# motor_MCU.net
KiCad netlist of a schematic drawn in Altium Designer
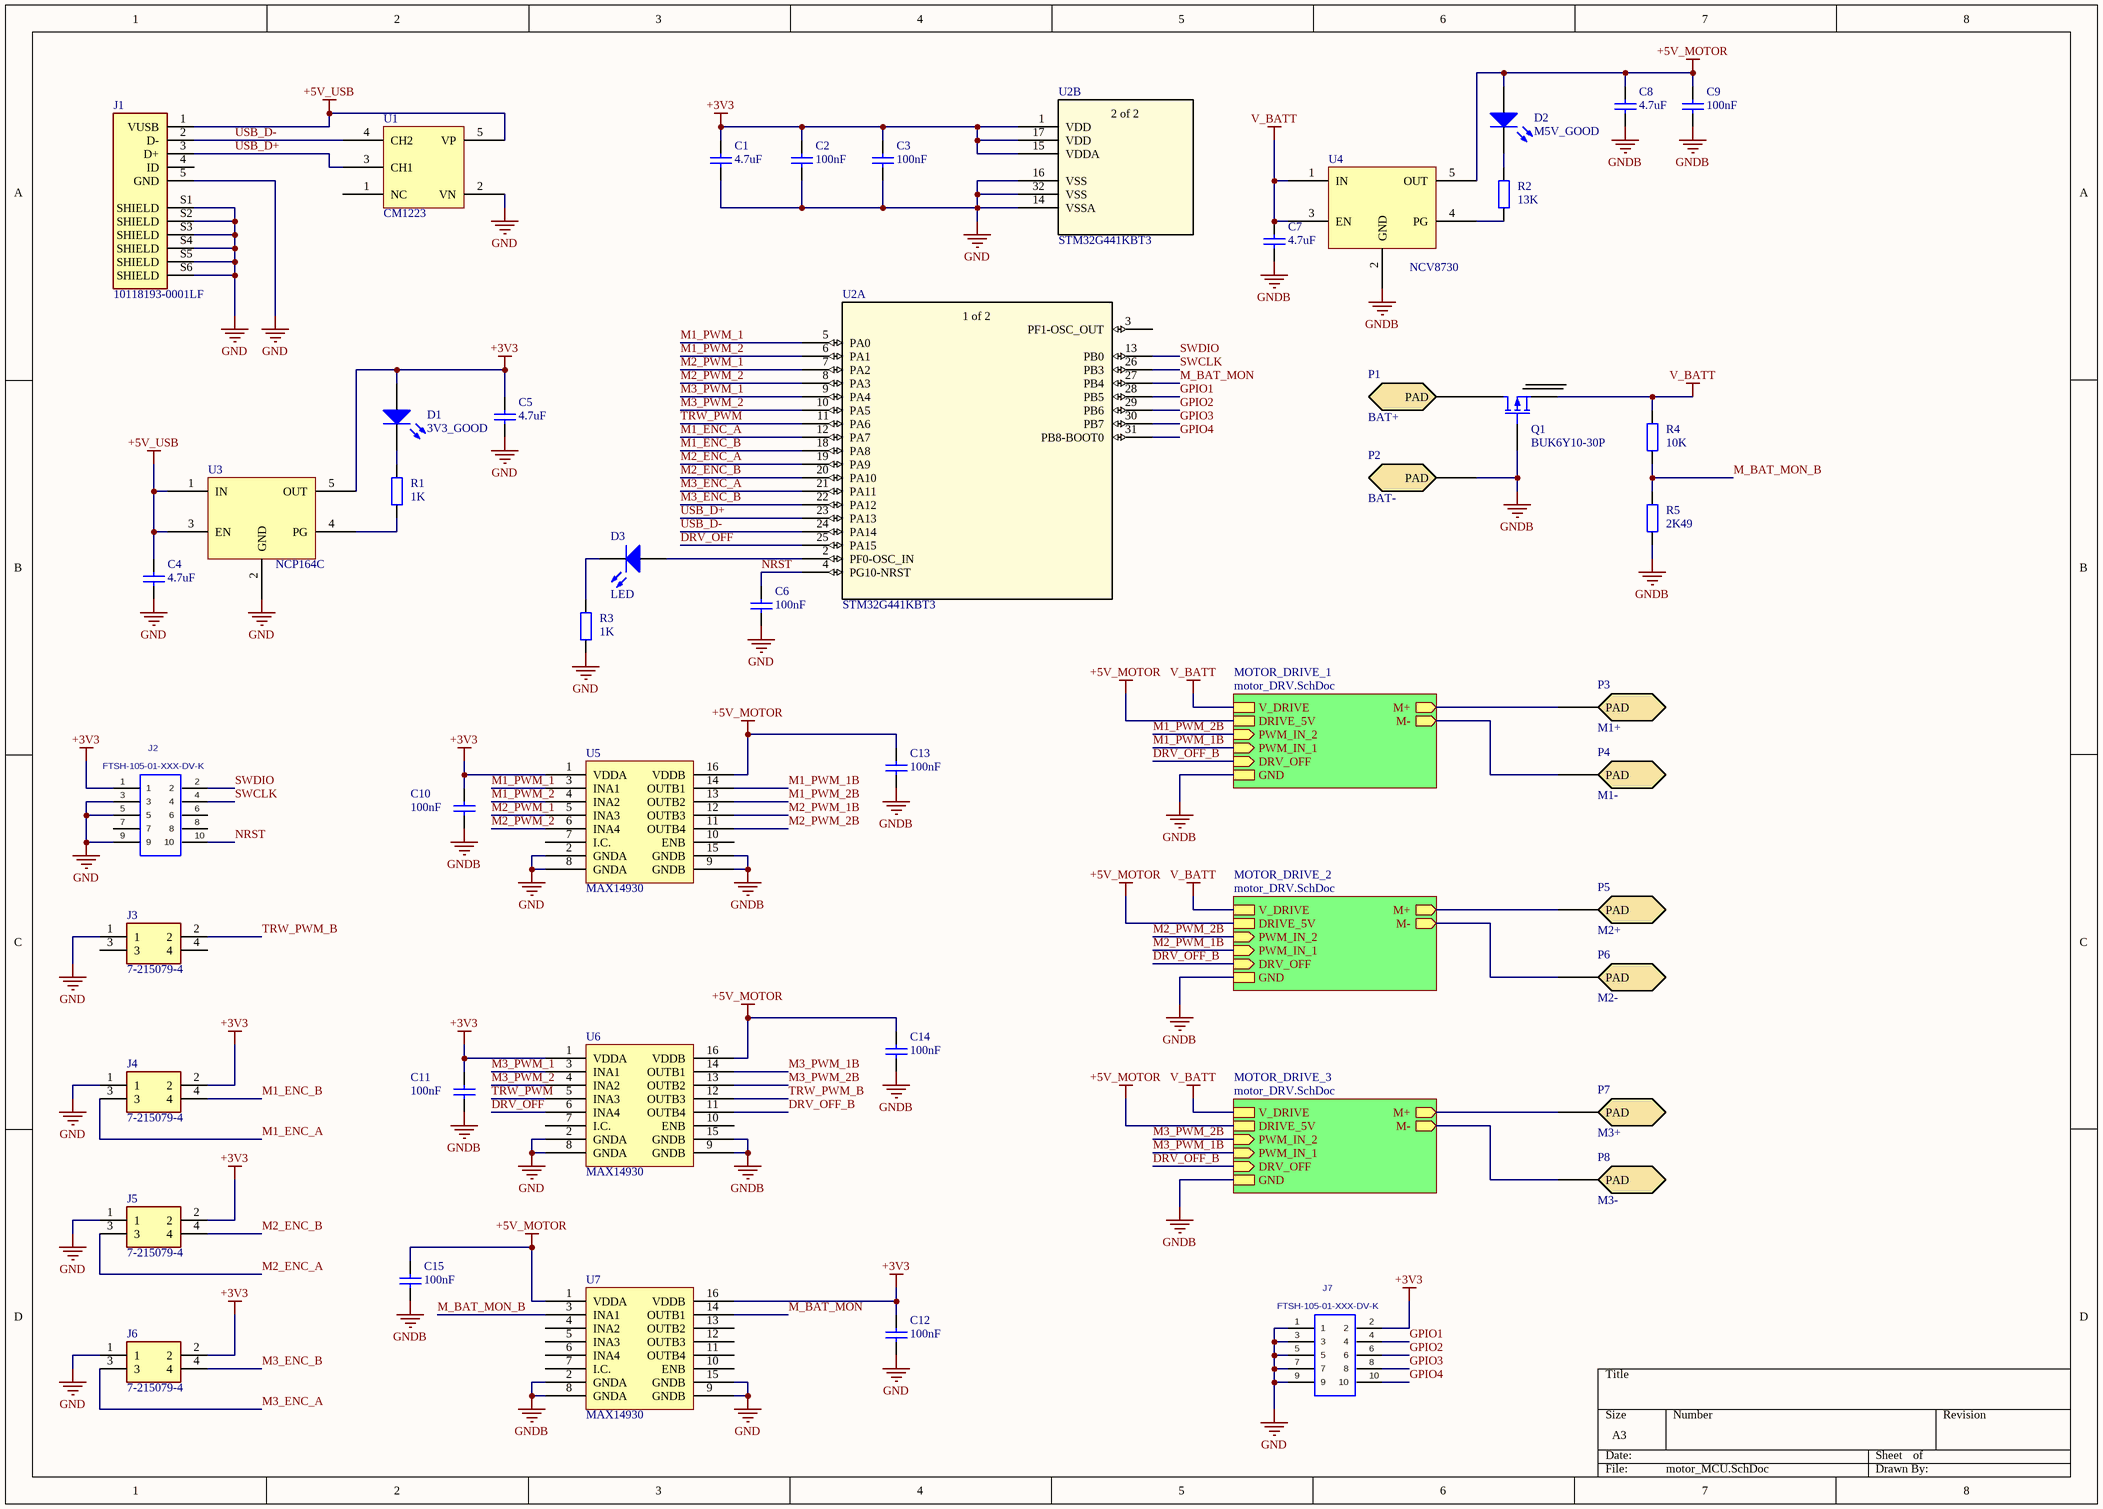
[diagram p0: motor_MCU.SchDoc]

(export (version "E")
  (design (tool "Eeschema 10.0.6"))
  (components
    (comp (ref "C1")
      (value "4.7uF")
      (footprint "C1206")
      (description "Capacitor (Semiconductor SIM Model)")
      (fields (field (name "Comment") "Cap Semi") (field (name "PUBLISHER") "Altium Limited"))
      (libsource (lib "Miscellaneous Devices") (part "Cap Semi"))
    )
    (comp (ref "C2")
      (value "100nF")
      (footprint "1608[0603]")
      (description "Capacitor (Semiconductor SIM Model)")
      (fields (field (name "Comment") "Cap Semi") (field (name "PUBLISHER") "Altium Limited"))
      (libsource (lib "Miscellaneous Devices") (part "Cap Semi"))
    )
    (comp (ref "C3")
      (value "100nF")
      (footprint "1608[0603]")
      (description "Capacitor (Semiconductor SIM Model)")
      (fields (field (name "Comment") "Cap Semi") (field (name "PUBLISHER") "Altium Limited"))
      (libsource (lib "Miscellaneous Devices") (part "Cap Semi"))
    )
    (comp (ref "C4")
      (value "4.7uF")
      (footprint "C1206")
      (description "Capacitor (Semiconductor SIM Model)")
      (fields (field (name "Comment") "Cap Semi") (field (name "PUBLISHER") "Altium Limited"))
      (libsource (lib "Miscellaneous Devices") (part "Cap Semi"))
    )
    (comp (ref "C5")
      (value "4.7uF")
      (footprint "C1206")
      (description "Capacitor (Semiconductor SIM Model)")
      (fields (field (name "Comment") "Cap Semi") (field (name "PUBLISHER") "Altium Limited"))
      (libsource (lib "Miscellaneous Devices") (part "Cap Semi"))
    )
    (comp (ref "C6")
      (value "100nF")
      (footprint "1608[0603]")
      (description "Capacitor (Semiconductor SIM Model)")
      (fields (field (name "Comment") "Cap Semi") (field (name "PUBLISHER") "Altium Limited"))
      (libsource (lib "Miscellaneous Devices") (part "Cap Semi"))
    )
    (comp (ref "C7")
      (value "4.7uF")
      (footprint "C1206")
      (description "Capacitor (Semiconductor SIM Model)")
      (fields (field (name "Comment") "Cap Semi") (field (name "PUBLISHER") "Altium Limited"))
      (libsource (lib "Miscellaneous Devices") (part "Cap Semi"))
    )
    (comp (ref "C8")
      (value "4.7uF")
      (footprint "C1206")
      (description "Capacitor (Semiconductor SIM Model)")
      (fields (field (name "Comment") "Cap Semi") (field (name "PUBLISHER") "Altium Limited"))
      (libsource (lib "Miscellaneous Devices") (part "Cap Semi"))
    )
    (comp (ref "C9")
      (value "100nF")
      (footprint "1608[0603]")
      (description "Capacitor (Semiconductor SIM Model)")
      (fields (field (name "Comment") "Cap Semi") (field (name "PUBLISHER") "Altium Limited"))
      (libsource (lib "Miscellaneous Devices") (part "Cap Semi"))
    )
    (comp (ref "C10")
      (value "100nF")
      (footprint "1608[0603]")
      (description "Capacitor (Semiconductor SIM Model)")
      (fields (field (name "Comment") "Cap Semi") (field (name "PUBLISHER") "Altium Limited"))
      (libsource (lib "Miscellaneous Devices") (part "Cap Semi"))
    )
    (comp (ref "C11")
      (value "100nF")
      (footprint "1608[0603]")
      (description "Capacitor (Semiconductor SIM Model)")
      (fields (field (name "Comment") "Cap Semi") (field (name "PUBLISHER") "Altium Limited"))
      (libsource (lib "Miscellaneous Devices") (part "Cap Semi"))
    )
    (comp (ref "C12")
      (value "100nF")
      (footprint "1608[0603]")
      (description "Capacitor (Semiconductor SIM Model)")
      (fields (field (name "Comment") "Cap Semi") (field (name "PUBLISHER") "Altium Limited"))
      (libsource (lib "Miscellaneous Devices") (part "Cap Semi"))
    )
    (comp (ref "C13")
      (value "100nF")
      (footprint "1608[0603]")
      (description "Capacitor (Semiconductor SIM Model)")
      (fields (field (name "Comment") "Cap Semi") (field (name "PUBLISHER") "Altium Limited"))
      (libsource (lib "Miscellaneous Devices") (part "Cap Semi"))
    )
    (comp (ref "C14")
      (value "100nF")
      (footprint "1608[0603]")
      (description "Capacitor (Semiconductor SIM Model)")
      (fields (field (name "Comment") "Cap Semi") (field (name "PUBLISHER") "Altium Limited"))
      (libsource (lib "Miscellaneous Devices") (part "Cap Semi"))
    )
    (comp (ref "C15")
      (value "100nF")
      (footprint "1608[0603]")
      (description "Capacitor (Semiconductor SIM Model)")
      (fields (field (name "Comment") "Cap Semi") (field (name "PUBLISHER") "Altium Limited"))
      (libsource (lib "Miscellaneous Devices") (part "Cap Semi"))
    )
    (comp (ref "D1")
      (value "3V3_GOOD")
      (footprint "3.2X1.6X1.1")
      (description "Typical RED, GREEN, YELLOW, AMBER GaAs LED")
      (fields (field (name "PUBLISHER") "Altium Limited"))
      (libsource (lib "Miscellaneous Devices") (part "LED2"))
    )
    (comp (ref "D2")
      (value "M5V_GOOD")
      (footprint "3.2X1.6X1.1")
      (description "Typical RED, GREEN, YELLOW, AMBER GaAs LED")
      (fields (field (name "PUBLISHER") "Altium Limited"))
      (libsource (lib "Miscellaneous Devices") (part "LED2"))
    )
    (comp (ref "D3")
      (value "LED")
      (footprint "3.2X1.6X1.1")
      (description "Typical RED, GREEN, YELLOW, AMBER GaAs LED")
      (fields (field (name "PUBLISHER") "Altium Limited"))
      (libsource (lib "Miscellaneous Devices") (part "LED2"))
    )
    (comp (ref "J1")
      (value "10118193-0001LF")
      (footprint "FCI_10118193-0001LF")
      (description "USB - micro B USB 2.0 Receptacle Connector 5 Position Surface Mount, Right Angle; Through Hole")
      (fields (field (name "MF") "Amphenol ICC"))
      (libsource (lib "10118193-0001LF") (part "10118193-0001LF"))
    )
    (comp (ref "J2")
      (value "FTSH-105-01-XXX-DV-K")
      (footprint "FTSH-105-01-XXX-DV-K")
      (description "TERMINAL STRIP, .050\"(1.27mm) PITCH, 10 PINS, KEYED")
      (fields (field (name "MANUFACTURER") "SAMTEC") (field (name "CREATED") "November 30, 2016 - Wendy Xin"))
      (libsource (lib "FTSH-105-01-XXX-DV-K--Symbol-Altium-44987") (part "FTSH-105-01-XXX-DV-K"))
    )
    (comp (ref "J3")
      (value "7-215079-4")
      (footprint "TE_7-215079-4")
      (description "Micro-MaTch 4 Position 1.27 mm Pitch Vertical Female-on-Board Connector")
      (fields (field (name "MF") "TE Connectivity"))
      (libsource (lib "7-215079-4") (part "7-215079-4"))
    )
    (comp (ref "J4")
      (value "7-215079-4")
      (footprint "TE_7-215079-4")
      (description "Micro-MaTch 4 Position 1.27 mm Pitch Vertical Female-on-Board Connector")
      (fields (field (name "MF") "TE Connectivity"))
      (libsource (lib "7-215079-4") (part "7-215079-4"))
    )
    (comp (ref "J5")
      (value "7-215079-4")
      (footprint "TE_7-215079-4")
      (description "Micro-MaTch 4 Position 1.27 mm Pitch Vertical Female-on-Board Connector")
      (fields (field (name "MF") "TE Connectivity"))
      (libsource (lib "7-215079-4") (part "7-215079-4"))
    )
    (comp (ref "J6")
      (value "7-215079-4")
      (footprint "TE_7-215079-4")
      (description "Micro-MaTch 4 Position 1.27 mm Pitch Vertical Female-on-Board Connector")
      (fields (field (name "MF") "TE Connectivity"))
      (libsource (lib "7-215079-4") (part "7-215079-4"))
    )
    (comp (ref "J7")
      (value "FTSH-105-01-XXX-DV-K")
      (footprint "FTSH-105-01-XXX-DV-K")
      (description "TERMINAL STRIP, .050\"(1.27mm) PITCH, 10 PINS, KEYED")
      (fields (field (name "MANUFACTURER") "SAMTEC") (field (name "CREATED") "November 30, 2016 - Wendy Xin"))
      (libsource (lib "FTSH-105-01-XXX-DV-K--Symbol-Altium-44987") (part "FTSH-105-01-XXX-DV-K"))
    )
    (comp (ref "P1")
      (value "BAT+")
      (footprint "PCBComponent_1")
      (libsource (lib "powerpad140x175") (part "Component_1"))
    )
    (comp (ref "P2")
      (value "BAT-")
      (footprint "PCBComponent_1")
      (libsource (lib "powerpad140x175") (part "Component_1"))
    )
    (comp (ref "P3")
      (value "M1+")
      (footprint "PCBComponent_1")
      (libsource (lib "powerpad140x175") (part "Component_1"))
    )
    (comp (ref "P4")
      (value "M1-")
      (footprint "PCBComponent_1")
      (libsource (lib "powerpad140x175") (part "Component_1"))
    )
    (comp (ref "P5")
      (value "M2+")
      (footprint "PCBComponent_1")
      (libsource (lib "powerpad140x175") (part "Component_1"))
    )
    (comp (ref "P6")
      (value "M2-")
      (footprint "PCBComponent_1")
      (libsource (lib "powerpad140x175") (part "Component_1"))
    )
    (comp (ref "P7")
      (value "M3+")
      (footprint "PCBComponent_1")
      (libsource (lib "powerpad140x175") (part "Component_1"))
    )
    (comp (ref "P8")
      (value "M3-")
      (footprint "PCBComponent_1")
      (libsource (lib "powerpad140x175") (part "Component_1"))
    )
    (comp (ref "Q1")
      (value "BUK6Y10-30P")
      (footprint "TO127P600X120-5N")
      (description "P-Channel MOSFET")
      (fields (field (name "PUBLISHER") "Altium Limited"))
      (libsource (lib "Miscellaneous Devices") (part "MOSFET-P"))
    )
    (comp (ref "R1")
      (value "1K")
      (footprint "CAPC2012X135N")
      (description "Resistor")
      (fields (field (name "Comment") "Res2") (field (name "PUBLISHER") "Altium Limited"))
      (libsource (lib "Miscellaneous Devices") (part "Res2"))
    )
    (comp (ref "R2")
      (value "13K")
      (footprint "CAPC2012X135N")
      (description "Resistor")
      (fields (field (name "Comment") "Res2") (field (name "PUBLISHER") "Altium Limited"))
      (libsource (lib "Miscellaneous Devices") (part "Res2"))
    )
    (comp (ref "R3")
      (value "1K")
      (footprint "CAPC2012X135N")
      (description "Resistor")
      (fields (field (name "Comment") "Res2") (field (name "PUBLISHER") "Altium Limited"))
      (libsource (lib "Miscellaneous Devices") (part "Res2"))
    )
    (comp (ref "R4")
      (value "10K")
      (footprint "CAPC2012X135N")
      (description "Resistor")
      (fields (field (name "Comment") "Res2") (field (name "PUBLISHER") "Altium Limited"))
      (libsource (lib "Miscellaneous Devices") (part "Res2"))
    )
    (comp (ref "R5")
      (value "2K49")
      (footprint "CAPC2012X135N")
      (description "Resistor")
      (fields (field (name "Comment") "Res2") (field (name "PUBLISHER") "Altium Limited"))
      (libsource (lib "Miscellaneous Devices") (part "Res2"))
    )
    (comp (ref "U1") (value "CM1223") (footprint "SOT23-5") (libsource (lib "CM1223-02SO") (part "CM1223")))
    (comp (ref "U2")
      (value "STM32G441KBT3")
      (footprint "LQFP32_7X7_STM")
      (description "No Description Available")
      (fields (field (name "COPYRIGHT") "Copyright (C) 2018 Accelerated Designs. All rights reserved"))
      (libsource (lib "STM32G441KBT3") (part "STM32G441KBT3"))
    )
    (comp (ref "U3") (value "NCP164C") (footprint "SOT23-5") (libsource (lib "NCP164C") (part "NCP164C")))
    (comp (ref "U4")
      (value "NCV8730")
      (footprint "TSSOP5")
      (description "5V LDO")
      (libsource (lib "NCV8730") (part "NCV8730"))
    )
    (comp (ref "U5")
      (value "MAX14930")
      (footprint "SOIC127P1030X265-16N")
      (libsource (lib "MAX14930") (part "MAX14930"))
    )
    (comp (ref "U6")
      (value "MAX14930")
      (footprint "SOIC127P1030X265-16N")
      (libsource (lib "MAX14930") (part "MAX14930"))
    )
    (comp (ref "U7")
      (value "MAX14930")
      (footprint "SOIC127P1030X265-16N")
      (libsource (lib "MAX14930") (part "MAX14930"))
    )
  )
  (nets
    (net (code "1") (name "+3V3") (class "Default")
      (node (ref "C1") (pin "2") (pinfunction "2_2") (pintype "passive"))
      (node (ref "C10") (pin "2") (pinfunction "2_2") (pintype "passive"))
      (node (ref "C11") (pin "2") (pinfunction "2_2") (pintype "passive"))
      (node (ref "C12") (pin "2") (pinfunction "2_2") (pintype "passive"))
      (node (ref "C2") (pin "2") (pinfunction "2_2") (pintype "passive"))
      (node (ref "C3") (pin "2") (pinfunction "2_2") (pintype "passive"))
      (node (ref "C5") (pin "2") (pinfunction "2_2") (pintype "passive"))
      (node (ref "D1") (pin "1") (pinfunction "A_1") (pintype "passive"))
      (node (ref "J2") (pin "1") (pinfunction "1_1") (pintype "passive"))
      (node (ref "J4") (pin "2") (pinfunction "2_2") (pintype "passive"))
      (node (ref "J5") (pin "2") (pinfunction "2_2") (pintype "passive"))
      (node (ref "J6") (pin "2") (pinfunction "2_2") (pintype "passive"))
      (node (ref "J7") (pin "2") (pinfunction "2_2") (pintype "passive"))
      (node (ref "U2") (pin "1") (pinfunction "VDD_1") (pintype "power_in"))
      (node (ref "U2") (pin "15") (pinfunction "VDDA_15") (pintype "power_in"))
      (node (ref "U2") (pin "17") (pinfunction "VDD_17") (pintype "power_in"))
      (node (ref "U3") (pin "5") (pinfunction "OUT_5") (pintype "passive"))
      (node (ref "U5") (pin "1") (pinfunction "VDDA_1") (pintype "passive"))
      (node (ref "U6") (pin "1") (pinfunction "VDDA_1") (pintype "passive"))
      (node (ref "U7") (pin "16") (pinfunction "VDDB_16") (pintype "passive"))
    )
    (net (code "2") (name "+5V_MOTOR") (class "Default")
      (node (ref "C13") (pin "2") (pinfunction "2_2") (pintype "passive"))
      (node (ref "C14") (pin "2") (pinfunction "2_2") (pintype "passive"))
      (node (ref "C15") (pin "2") (pinfunction "2_2") (pintype "passive"))
      (node (ref "C8") (pin "2") (pinfunction "2_2") (pintype "passive"))
      (node (ref "C9") (pin "2") (pinfunction "2_2") (pintype "passive"))
      (node (ref "D2") (pin "1") (pinfunction "A_1") (pintype "passive"))
      (node (ref "U4") (pin "5") (pinfunction "OUT_5") (pintype "passive"))
      (node (ref "U5") (pin "16") (pinfunction "VDDB_16") (pintype "passive"))
      (node (ref "U6") (pin "16") (pinfunction "VDDB_16") (pintype "passive"))
      (node (ref "U7") (pin "1") (pinfunction "VDDA_1") (pintype "passive"))
    )
    (net (code "3") (name "+5V_USB") (class "Default")
      (node (ref "C4") (pin "2") (pinfunction "2_2") (pintype "passive"))
      (node (ref "J1") (pin "1") (pinfunction "VUSB_1") (pintype "passive"))
      (node (ref "U1") (pin "5") (pinfunction "VP_5") (pintype "passive"))
      (node (ref "U3") (pin "1") (pinfunction "IN_1") (pintype "passive"))
      (node (ref "U3") (pin "3") (pinfunction "EN_3") (pintype "passive"))
    )
    (net (code "4") (name "/DRV_OFF") (class "Default")
      (node (ref "U2") (pin "25") (pinfunction "PA15_25") (pintype "bidirectional"))
      (node (ref "U6") (pin "6") (pinfunction "INA4_6") (pintype "passive"))
    )
    (net (code "5") (name "/DRV_OFF_B") (class "Default")
      (node (ref "U6") (pin "11") (pinfunction "OUTB4_11") (pintype "passive"))
    )
    (net (code "6") (name "/GPIO1") (class "Default")
      (node (ref "J7") (pin "4") (pinfunction "4_4") (pintype "passive"))
      (node (ref "U2") (pin "28") (pinfunction "PB5_28") (pintype "bidirectional"))
    )
    (net (code "7") (name "/GPIO2") (class "Default")
      (node (ref "J7") (pin "6") (pinfunction "6_6") (pintype "passive"))
      (node (ref "U2") (pin "29") (pinfunction "PB6_29") (pintype "bidirectional"))
    )
    (net (code "8") (name "/GPIO3") (class "Default")
      (node (ref "J7") (pin "8") (pinfunction "8_8") (pintype "passive"))
      (node (ref "U2") (pin "30") (pinfunction "PB7_30") (pintype "bidirectional"))
    )
    (net (code "9") (name "/GPIO4") (class "Default")
      (node (ref "J7") (pin "10") (pinfunction "10_10") (pintype "passive"))
      (node (ref "U2") (pin "31") (pinfunction "PB8-BOOT0_31") (pintype "bidirectional"))
    )
    (net (code "10") (name "/M+") (class "Default")
      (node (ref "P7") (pin "1") (pinfunction "PAD_1") (pintype "passive"))
    )
    (net (code "11") (name "/M+_1") (class "Default")
      (node (ref "P3") (pin "1") (pinfunction "PAD_1") (pintype "passive"))
    )
    (net (code "12") (name "/M+_2") (class "Default")
      (node (ref "P5") (pin "1") (pinfunction "PAD_1") (pintype "passive"))
    )
    (net (code "13") (name "/M-") (class "Default")
      (node (ref "P8") (pin "1") (pinfunction "PAD_1") (pintype "passive"))
    )
    (net (code "14") (name "/M-_1") (class "Default")
      (node (ref "P4") (pin "1") (pinfunction "PAD_1") (pintype "passive"))
    )
    (net (code "15") (name "/M-_2") (class "Default")
      (node (ref "P6") (pin "1") (pinfunction "PAD_1") (pintype "passive"))
    )
    (net (code "16") (name "/M1_ENC_A") (class "Default")
      (node (ref "J4") (pin "3") (pinfunction "3_3") (pintype "passive"))
      (node (ref "U2") (pin "12") (pinfunction "PA7_12") (pintype "bidirectional"))
    )
    (net (code "17") (name "/M1_ENC_B") (class "Default")
      (node (ref "J4") (pin "4") (pinfunction "4_4") (pintype "passive"))
      (node (ref "U2") (pin "18") (pinfunction "PA8_18") (pintype "bidirectional"))
    )
    (net (code "18") (name "/M1_PWM_1") (class "Default")
      (node (ref "U2") (pin "5") (pinfunction "PA0_5") (pintype "bidirectional"))
      (node (ref "U5") (pin "3") (pinfunction "INA1_3") (pintype "passive"))
    )
    (net (code "19") (name "/M1_PWM_1B") (class "Default")
      (node (ref "U5") (pin "14") (pinfunction "OUTB1_14") (pintype "passive"))
    )
    (net (code "20") (name "/M1_PWM_2") (class "Default")
      (node (ref "U2") (pin "6") (pinfunction "PA1_6") (pintype "bidirectional"))
      (node (ref "U5") (pin "4") (pinfunction "INA2_4") (pintype "passive"))
    )
    (net (code "21") (name "/M1_PWM_2B") (class "Default")
      (node (ref "U5") (pin "13") (pinfunction "OUTB2_13") (pintype "passive"))
    )
    (net (code "22") (name "/M2_ENC_A") (class "Default")
      (node (ref "J5") (pin "3") (pinfunction "3_3") (pintype "passive"))
      (node (ref "U2") (pin "19") (pinfunction "PA9_19") (pintype "bidirectional"))
    )
    (net (code "23") (name "/M2_ENC_B") (class "Default")
      (node (ref "J5") (pin "4") (pinfunction "4_4") (pintype "passive"))
      (node (ref "U2") (pin "20") (pinfunction "PA10_20") (pintype "bidirectional"))
    )
    (net (code "24") (name "/M2_PWM_1") (class "Default")
      (node (ref "U2") (pin "7") (pinfunction "PA2_7") (pintype "bidirectional"))
      (node (ref "U5") (pin "5") (pinfunction "INA3_5") (pintype "passive"))
    )
    (net (code "25") (name "/M2_PWM_1B") (class "Default")
      (node (ref "U5") (pin "12") (pinfunction "OUTB3_12") (pintype "passive"))
    )
    (net (code "26") (name "/M2_PWM_2") (class "Default")
      (node (ref "U2") (pin "8") (pinfunction "PA3_8") (pintype "bidirectional"))
      (node (ref "U5") (pin "6") (pinfunction "INA4_6") (pintype "passive"))
    )
    (net (code "27") (name "/M2_PWM_2B") (class "Default")
      (node (ref "U5") (pin "11") (pinfunction "OUTB4_11") (pintype "passive"))
    )
    (net (code "28") (name "/M3_ENC_A") (class "Default")
      (node (ref "J6") (pin "3") (pinfunction "3_3") (pintype "passive"))
      (node (ref "U2") (pin "21") (pinfunction "PA11_21") (pintype "bidirectional"))
    )
    (net (code "29") (name "/M3_ENC_B") (class "Default")
      (node (ref "J6") (pin "4") (pinfunction "4_4") (pintype "passive"))
      (node (ref "U2") (pin "22") (pinfunction "PA12_22") (pintype "bidirectional"))
    )
    (net (code "30") (name "/M3_PWM_1") (class "Default")
      (node (ref "U2") (pin "9") (pinfunction "PA4_9") (pintype "bidirectional"))
      (node (ref "U6") (pin "3") (pinfunction "INA1_3") (pintype "passive"))
    )
    (net (code "31") (name "/M3_PWM_1B") (class "Default")
      (node (ref "U6") (pin "14") (pinfunction "OUTB1_14") (pintype "passive"))
    )
    (net (code "32") (name "/M3_PWM_2") (class "Default")
      (node (ref "U2") (pin "10") (pinfunction "PA5_10") (pintype "bidirectional"))
      (node (ref "U6") (pin "4") (pinfunction "INA2_4") (pintype "passive"))
    )
    (net (code "33") (name "/M3_PWM_2B") (class "Default")
      (node (ref "U6") (pin "13") (pinfunction "OUTB2_13") (pintype "passive"))
    )
    (net (code "34") (name "/M_BAT_MON") (class "Default")
      (node (ref "U2") (pin "27") (pinfunction "PB4_27") (pintype "bidirectional"))
      (node (ref "U7") (pin "14") (pinfunction "OUTB1_14") (pintype "passive"))
    )
    (net (code "35") (name "/M_BAT_MON_B") (class "Default")
      (node (ref "R4") (pin "1") (pinfunction "1_1") (pintype "passive"))
      (node (ref "R5") (pin "2") (pinfunction "2_2") (pintype "passive"))
      (node (ref "U7") (pin "3") (pinfunction "INA1_3") (pintype "passive"))
    )
    (net (code "36") (name "/NRST") (class "Default")
      (node (ref "C6") (pin "2") (pinfunction "2_2") (pintype "passive"))
      (node (ref "J2") (pin "10") (pinfunction "10_10") (pintype "passive"))
      (node (ref "U2") (pin "4") (pinfunction "PG10-NRST_4") (pintype "bidirectional"))
    )
    (net (code "37") (name "/SWCLK") (class "Default")
      (node (ref "J2") (pin "4") (pinfunction "4_4") (pintype "passive"))
      (node (ref "U2") (pin "26") (pinfunction "PB3_26") (pintype "bidirectional"))
    )
    (net (code "38") (name "/SWDIO") (class "Default")
      (node (ref "J2") (pin "2") (pinfunction "2_2") (pintype "passive"))
      (node (ref "U2") (pin "13") (pinfunction "PB0_13") (pintype "bidirectional"))
    )
    (net (code "39") (name "/TRW_PWM") (class "Default")
      (node (ref "U2") (pin "11") (pinfunction "PA6_11") (pintype "bidirectional"))
      (node (ref "U6") (pin "5") (pinfunction "INA3_5") (pintype "passive"))
    )
    (net (code "40") (name "/TRW_PWM_B") (class "Default")
      (node (ref "J3") (pin "2") (pinfunction "2_2") (pintype "passive"))
      (node (ref "U6") (pin "12") (pinfunction "OUTB3_12") (pintype "passive"))
    )
    (net (code "41") (name "/USB_D+") (class "Default")
      (node (ref "J1") (pin "3") (pinfunction "D+_3") (pintype "passive"))
      (node (ref "U1") (pin "3") (pinfunction "CH1_3") (pintype "passive"))
      (node (ref "U2") (pin "23") (pinfunction "PA13_23") (pintype "bidirectional"))
    )
    (net (code "42") (name "/USB_D-") (class "Default")
      (node (ref "J1") (pin "2") (pinfunction "D-_2") (pintype "passive"))
      (node (ref "U1") (pin "4") (pinfunction "CH2_4") (pintype "passive"))
      (node (ref "U2") (pin "24") (pinfunction "PA14_24") (pintype "bidirectional"))
    )
    (net (code "43") (name "GND") (class "Default")
      (node (ref "C1") (pin "1") (pinfunction "1_1") (pintype "passive"))
      (node (ref "C12") (pin "1") (pinfunction "1_1") (pintype "passive"))
      (node (ref "C2") (pin "1") (pinfunction "1_1") (pintype "passive"))
      (node (ref "C3") (pin "1") (pinfunction "1_1") (pintype "passive"))
      (node (ref "C4") (pin "1") (pinfunction "1_1") (pintype "passive"))
      (node (ref "C5") (pin "1") (pinfunction "1_1") (pintype "passive"))
      (node (ref "C6") (pin "1") (pinfunction "1_1") (pintype "passive"))
      (node (ref "J1") (pin "5") (pinfunction "GND_5") (pintype "passive"))
      (node (ref "J1") (pin "S1") (pinfunction "SHIELD_S1") (pintype "passive"))
      (node (ref "J1") (pin "S2") (pinfunction "SHIELD_S2") (pintype "passive"))
      (node (ref "J1") (pin "S3") (pinfunction "SHIELD_S3") (pintype "passive"))
      (node (ref "J1") (pin "S4") (pinfunction "SHIELD_S4") (pintype "passive"))
      (node (ref "J1") (pin "S5") (pinfunction "SHIELD_S5") (pintype "passive"))
      (node (ref "J1") (pin "S6") (pinfunction "SHIELD_S6") (pintype "passive"))
      (node (ref "J2") (pin "3") (pinfunction "3_3") (pintype "passive"))
      (node (ref "J2") (pin "5") (pinfunction "5_5") (pintype "passive"))
      (node (ref "J2") (pin "9") (pinfunction "9_9") (pintype "passive"))
      (node (ref "J3") (pin "1") (pinfunction "1_1") (pintype "passive"))
      (node (ref "J4") (pin "1") (pinfunction "1_1") (pintype "passive"))
      (node (ref "J5") (pin "1") (pinfunction "1_1") (pintype "passive"))
      (node (ref "J6") (pin "1") (pinfunction "1_1") (pintype "passive"))
      (node (ref "J7") (pin "1") (pinfunction "1_1") (pintype "passive"))
      (node (ref "J7") (pin "3") (pinfunction "3_3") (pintype "passive"))
      (node (ref "J7") (pin "5") (pinfunction "5_5") (pintype "passive"))
      (node (ref "J7") (pin "7") (pinfunction "7_7") (pintype "passive"))
      (node (ref "J7") (pin "9") (pinfunction "9_9") (pintype "passive"))
      (node (ref "R3") (pin "1") (pinfunction "1_1") (pintype "passive"))
      (node (ref "U1") (pin "2") (pinfunction "VN_2") (pintype "passive"))
      (node (ref "U2") (pin "14") (pinfunction "VSSA_14") (pintype "passive"))
      (node (ref "U2") (pin "16") (pinfunction "VSS_16") (pintype "passive"))
      (node (ref "U2") (pin "32") (pinfunction "VSS_32") (pintype "passive"))
      (node (ref "U3") (pin "2") (pinfunction "GND_2") (pintype "passive"))
      (node (ref "U5") (pin "2") (pinfunction "GNDA_2") (pintype "passive"))
      (node (ref "U5") (pin "8") (pinfunction "GNDA_8") (pintype "passive"))
      (node (ref "U6") (pin "2") (pinfunction "GNDA_2") (pintype "passive"))
      (node (ref "U6") (pin "8") (pinfunction "GNDA_8") (pintype "passive"))
      (node (ref "U7") (pin "15") (pinfunction "GNDB_15") (pintype "passive"))
      (node (ref "U7") (pin "9") (pinfunction "GNDB_9") (pintype "passive"))
    )
    (net (code "44") (name "GNDB") (class "Default")
      (node (ref "C10") (pin "1") (pinfunction "1_1") (pintype "passive"))
      (node (ref "C11") (pin "1") (pinfunction "1_1") (pintype "passive"))
      (node (ref "C13") (pin "1") (pinfunction "1_1") (pintype "passive"))
      (node (ref "C14") (pin "1") (pinfunction "1_1") (pintype "passive"))
      (node (ref "C15") (pin "1") (pinfunction "1_1") (pintype "passive"))
      (node (ref "C7") (pin "1") (pinfunction "1_1") (pintype "passive"))
      (node (ref "C8") (pin "1") (pinfunction "1_1") (pintype "passive"))
      (node (ref "C9") (pin "1") (pinfunction "1_1") (pintype "passive"))
      (node (ref "P2") (pin "1") (pinfunction "PAD_1") (pintype "passive"))
      (node (ref "Q1") (pin "2") (pinfunction "S_2") (pintype "passive"))
      (node (ref "R5") (pin "1") (pinfunction "1_1") (pintype "passive"))
      (node (ref "U4") (pin "2") (pinfunction "GND_2") (pintype "passive"))
      (node (ref "U5") (pin "15") (pinfunction "GNDB_15") (pintype "passive"))
      (node (ref "U5") (pin "9") (pinfunction "GNDB_9") (pintype "passive"))
      (node (ref "U6") (pin "15") (pinfunction "GNDB_15") (pintype "passive"))
      (node (ref "U6") (pin "9") (pinfunction "GNDB_9") (pintype "passive"))
      (node (ref "U7") (pin "2") (pinfunction "GNDA_2") (pintype "passive"))
      (node (ref "U7") (pin "8") (pinfunction "GNDA_8") (pintype "passive"))
    )
    (net (code "45") (name "Net-(D1-K)") (class "Default")
      (node (ref "D1") (pin "2") (pinfunction "K_2") (pintype "passive"))
      (node (ref "R1") (pin "2") (pinfunction "2_2") (pintype "passive"))
    )
    (net (code "46") (name "Net-(D2-K)") (class "Default")
      (node (ref "D2") (pin "2") (pinfunction "K_2") (pintype "passive"))
      (node (ref "R2") (pin "2") (pinfunction "2_2") (pintype "passive"))
    )
    (net (code "47") (name "Net-(D3-A)") (class "Default")
      (node (ref "D3") (pin "1") (pinfunction "A_1") (pintype "passive"))
      (node (ref "U2") (pin "2") (pinfunction "PF0-OSC_IN_2") (pintype "bidirectional"))
    )
    (net (code "48") (name "Net-(D3-K)") (class "Default")
      (node (ref "D3") (pin "2") (pinfunction "K_2") (pintype "passive"))
      (node (ref "R3") (pin "2") (pinfunction "2_2") (pintype "passive"))
    )
    (net (code "49") (name "Net-(P1-PAD)") (class "Default")
      (node (ref "P1") (pin "1") (pinfunction "PAD_1") (pintype "passive"))
      (node (ref "Q1") (pin "1") (pinfunction "S_1") (pintype "passive"))
    )
    (net (code "50") (name "Net-(U3-PG)") (class "Default")
      (node (ref "R1") (pin "1") (pinfunction "1_1") (pintype "passive"))
      (node (ref "U3") (pin "4") (pinfunction "PG_4") (pintype "passive"))
    )
    (net (code "51") (name "Net-(U4-PG)") (class "Default")
      (node (ref "R2") (pin "1") (pinfunction "1_1") (pintype "passive"))
      (node (ref "U4") (pin "4") (pinfunction "PG_4") (pintype "passive"))
    )
    (net (code "52") (name "V_BATT") (class "Default")
      (node (ref "C7") (pin "2") (pinfunction "2_2") (pintype "passive"))
      (node (ref "Q1") (pin "3") (pinfunction "S_3") (pintype "passive"))
      (node (ref "R4") (pin "2") (pinfunction "2_2") (pintype "passive"))
      (node (ref "U4") (pin "1") (pinfunction "IN_1") (pintype "passive"))
      (node (ref "U4") (pin "3") (pinfunction "EN_3") (pintype "passive"))
    )
    (net (code "53") (name "unconnected-(J1-ID-Pad4)") (class "Default")
      (node (ref "J1") (pin "4") (pinfunction "ID_4") (pintype "passive"))
    )
    (net (code "54") (name "unconnected-(J2-Pad6)") (class "Default")
      (node (ref "J2") (pin "6") (pinfunction "6_6") (pintype "passive"))
    )
    (net (code "55") (name "unconnected-(J2-Pad7)") (class "Default")
      (node (ref "J2") (pin "7") (pinfunction "7_7") (pintype "passive"))
    )
    (net (code "56") (name "unconnected-(J2-Pad8)") (class "Default")
      (node (ref "J2") (pin "8") (pinfunction "8_8") (pintype "passive"))
    )
    (net (code "57") (name "unconnected-(J3-Pad3)") (class "Default")
      (node (ref "J3") (pin "3") (pinfunction "3_3") (pintype "passive"))
    )
    (net (code "58") (name "unconnected-(J3-Pad4)") (class "Default")
      (node (ref "J3") (pin "4") (pinfunction "4_4") (pintype "passive"))
    )
    (net (code "59") (name "unconnected-(Q1-D-Pad5)") (class "Default")
      (node (ref "Q1") (pin "5") (pinfunction "D_5") (pintype "passive"))
    )
    (net (code "60") (name "unconnected-(Q1-G-Pad4)") (class "Default")
      (node (ref "Q1") (pin "4") (pinfunction "G_4") (pintype "passive"))
    )
    (net (code "61") (name "unconnected-(U1-NC-Pad1)") (class "Default")
      (node (ref "U1") (pin "1") (pinfunction "NC_1") (pintype "passive"))
    )
    (net (code "62") (name "unconnected-(U2A-PF1-OSC_OUT-Pad3)") (class "Default")
      (node (ref "U2") (pin "3") (pinfunction "PF1-OSC_OUT_3") (pintype "bidirectional"))
    )
    (net (code "63") (name "unconnected-(U5-ENB-Pad10)") (class "Default")
      (node (ref "U5") (pin "10") (pinfunction "ENB_10") (pintype "passive"))
    )
    (net (code "64") (name "unconnected-(U5-I.C.-Pad7)") (class "Default")
      (node (ref "U5") (pin "7") (pinfunction "I.C._7") (pintype "passive"))
    )
    (net (code "65") (name "unconnected-(U6-ENB-Pad10)") (class "Default")
      (node (ref "U6") (pin "10") (pinfunction "ENB_10") (pintype "passive"))
    )
    (net (code "66") (name "unconnected-(U6-I.C.-Pad7)") (class "Default")
      (node (ref "U6") (pin "7") (pinfunction "I.C._7") (pintype "passive"))
    )
    (net (code "67") (name "unconnected-(U7-ENB-Pad10)") (class "Default")
      (node (ref "U7") (pin "10") (pinfunction "ENB_10") (pintype "passive"))
    )
    (net (code "68") (name "unconnected-(U7-I.C.-Pad7)") (class "Default")
      (node (ref "U7") (pin "7") (pinfunction "I.C._7") (pintype "passive"))
    )
    (net (code "69") (name "unconnected-(U7-INA2-Pad4)") (class "Default")
      (node (ref "U7") (pin "4") (pinfunction "INA2_4") (pintype "passive"))
    )
    (net (code "70") (name "unconnected-(U7-INA3-Pad5)") (class "Default")
      (node (ref "U7") (pin "5") (pinfunction "INA3_5") (pintype "passive"))
    )
    (net (code "71") (name "unconnected-(U7-INA4-Pad6)") (class "Default")
      (node (ref "U7") (pin "6") (pinfunction "INA4_6") (pintype "passive"))
    )
    (net (code "72") (name "unconnected-(U7-OUTB2-Pad13)") (class "Default")
      (node (ref "U7") (pin "13") (pinfunction "OUTB2_13") (pintype "passive"))
    )
    (net (code "73") (name "unconnected-(U7-OUTB3-Pad12)") (class "Default")
      (node (ref "U7") (pin "12") (pinfunction "OUTB3_12") (pintype "passive"))
    )
    (net (code "74") (name "unconnected-(U7-OUTB4-Pad11)") (class "Default")
      (node (ref "U7") (pin "11") (pinfunction "OUTB4_11") (pintype "passive"))
    )
  )
)
